# battery_regulator.net
KiCad netlist of a schematic drawn in Altium Designer
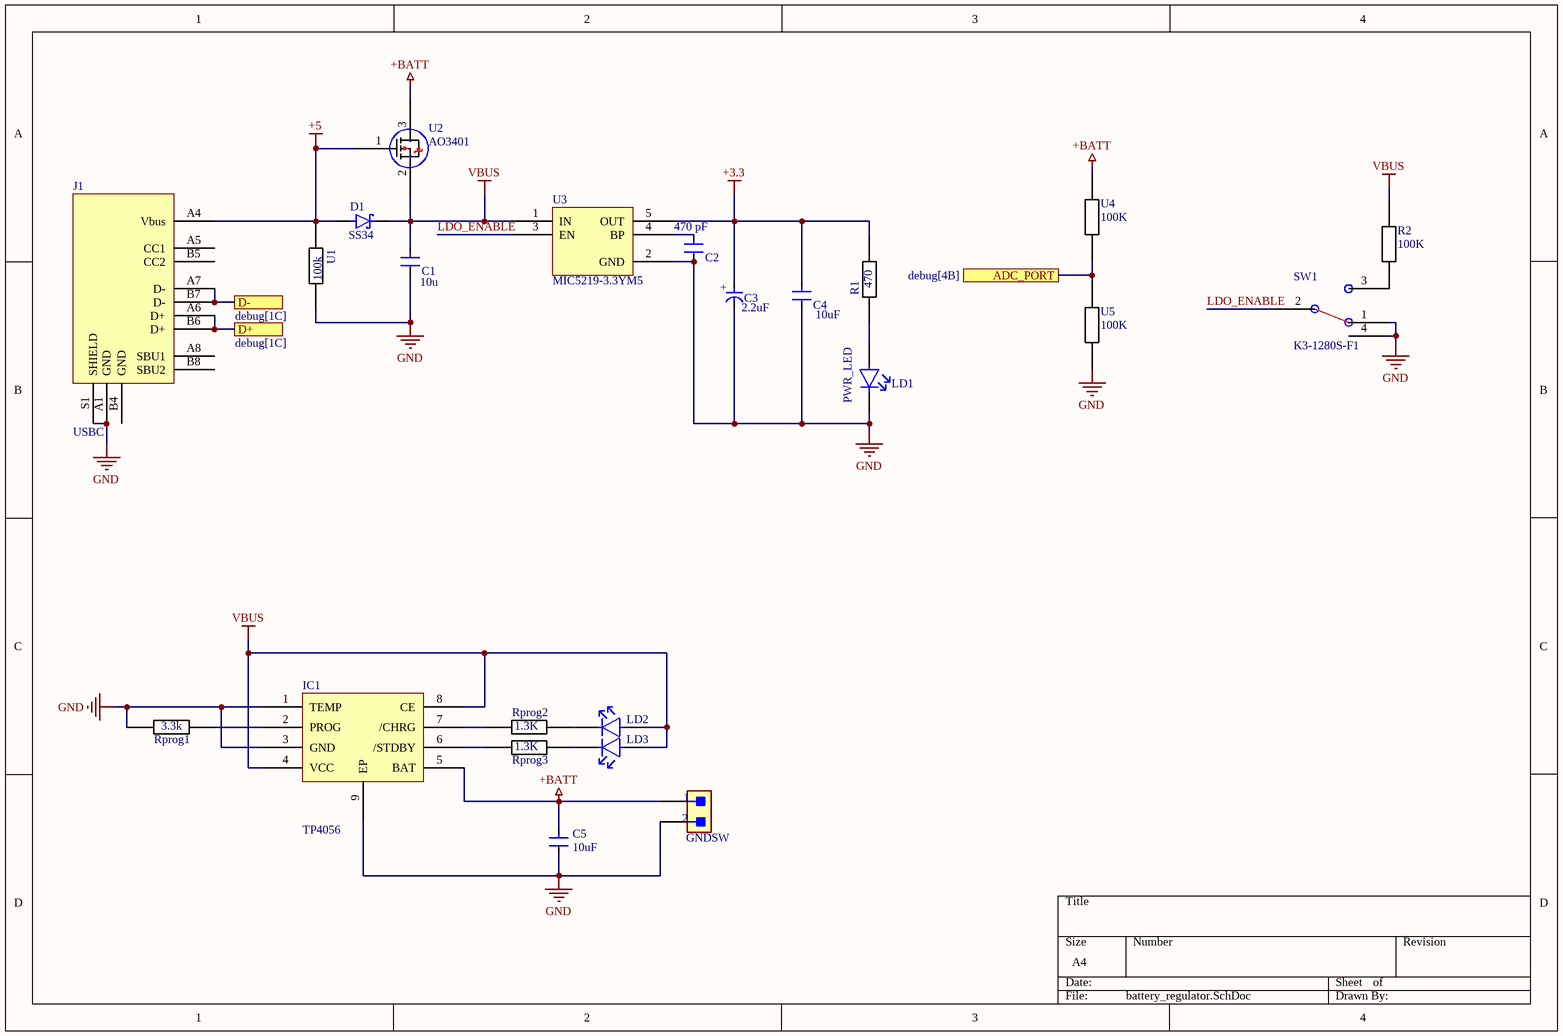
[diagram p0: battery_regulator.SchDoc]

(export (version "E")
  (design (tool "Eeschema 10.0.6"))
  (components
    (comp (ref "C1")
      (value "10u")
      (footprint "res0805ph")
      (fields (field (name "TOLERANCE") "20%"))
      (libsource (lib "LibraryTechnologie (1)") (part "CER Capacitor_1"))
    )
    (comp (ref "C2")
      (value "470 pF")
      (footprint "res0805ph")
      (fields (field (name "TOLERANCE") "20%"))
      (libsource (lib "LibraryTechnologie (1)") (part "CER Capacitor_1"))
    )
    (comp (ref "C3")
      (value "2.2uF")
      (footprint "res0805ph")
      (description "47uF 6.3V  ±20% 1.1Ω 2917  SMD Tantalum Capacitor")
      (fields (field (name "TOLERANCE") "20%"))
      (libsource (lib "LibraryTechnologie (1)") (part "Elco+tantaal_1"))
    )
    (comp (ref "C4")
      (value "10uF")
      (footprint "res0805ph")
      (fields (field (name "TOLERANCE") "20%"))
      (libsource (lib "LibraryTechnologie (1)") (part "CER Capacitor_1"))
    )
    (comp (ref "C5")
      (value "10uF")
      (footprint "res0805ph")
      (fields (field (name "TOLERANCE") "20%"))
      (libsource (lib "LibraryTechnologie (1)") (part "CER Capacitor_1"))
    )
    (comp (ref "D1") (value "SS34") (footprint "DIOM7959X265N") (libsource (lib "Dronesch") (part "SS34")))
    (comp (ref "GNDSW")
      (value "TMM-102-02-L-S")
      (footprint "JST_B2B-XH-A_(LF)(SN)")
      (description "CONN HEADER VERT 2POS 2MM")
      (libsource (lib "LibraryTechnologie (1)") (part "Connector 1x2_1"))
    )
    (comp (ref "IC1")
      (value "TP4056")
      (footprint "SOP127P600X175-9N")
      (libsource (lib "LibraryTechnologie (1)") (part "TP4056"))
    )
    (comp (ref "J1")
      (value "USBC")
      (footprint "SHENZHEN-CHUANGQIN-TECHNOLOGY_CQ-USB-C16PSMT01")
      (libsource (lib "Dronesch") (part "USBC"))
    )
    (comp (ref "LD1")
      (value "PWR_LED")
      (footprint "res0805ph")
      (description "LED GREEN CLEAR CHIP SMD")
      (libsource (lib "LibraryTechnologie (1)") (part "LED_1"))
    )
    (comp (ref "LD2")
      (value "APT1608ZGCK")
      (footprint "res0805ph")
      (description "LED GREEN CLEAR CHIP SMD")
      (libsource (lib "LibraryTechnologie (1)") (part "LED_1"))
    )
    (comp (ref "LD3")
      (value "APT1608ZGCK")
      (footprint "res0805ph")
      (description "LED GREEN CLEAR CHIP SMD")
      (libsource (lib "LibraryTechnologie (1)") (part "LED_1"))
    )
    (comp (ref "R1")
      (value "470")
      (footprint "res0805ph")
      (description "RES SMD 5.9K OHM 1% 1/4W 1206")
      (fields
        (field (name "OCTOPART") "https://octopart.com/ac1206fr-075k9l-yageo-30511161")
        (field (name "MANUFACTURER") "Yageo")
      )
      (libsource (lib "LibraryTechnologie (1)") (part "Weerstand_1"))
    )
    (comp (ref "R2")
      (value "100K")
      (footprint "res0805ph")
      (description "RES SMD 5.9K OHM 1% 1/4W 1206")
      (fields
        (field (name "OCTOPART") "https://octopart.com/ac1206fr-075k9l-yageo-30511161")
        (field (name "MANUFACTURER") "Yageo")
      )
      (libsource (lib "LibraryTechnologie (1)") (part "Weerstand_1"))
    )
    (comp (ref "Rprog1")
      (value "3.3k")
      (footprint "res0805ph")
      (description "RES SMD 5.9K OHM 1% 1/4W 1206")
      (fields
        (field (name "OCTOPART") "https://octopart.com/ac1206fr-075k9l-yageo-30511161")
        (field (name "MANUFACTURER") "Yageo")
      )
      (libsource (lib "LibraryTechnologie (1)") (part "Weerstand_1"))
    )
    (comp (ref "Rprog2")
      (value "1.3K")
      (footprint "res0805ph")
      (description "RES SMD 5.9K OHM 1% 1/4W 1206")
      (fields
        (field (name "OCTOPART") "https://octopart.com/ac1206fr-075k9l-yageo-30511161")
        (field (name "MANUFACTURER") "Yageo")
      )
      (libsource (lib "LibraryTechnologie (1)") (part "Weerstand_1"))
    )
    (comp (ref "Rprog3")
      (value "1.3K")
      (footprint "res0805ph")
      (description "RES SMD 5.9K OHM 1% 1/4W 1206")
      (fields
        (field (name "OCTOPART") "https://octopart.com/ac1206fr-075k9l-yageo-30511161")
        (field (name "MANUFACTURER") "Yageo")
      )
      (libsource (lib "LibraryTechnologie (1)") (part "Weerstand_1"))
    )
    (comp (ref "SW1")
      (value "K3-1280S-F1")
      (footprint "SW-SMD_K3-1280S-K1")
      (libsource (lib "Dronesch") (part "Switch"))
    )
    (comp (ref "U1")
      (value "100k")
      (footprint "res0805ph")
      (description "RES SMD 5.9K OHM 1% 1/4W 1206")
      (fields
        (field (name "OCTOPART") "https://octopart.com/ac1206fr-075k9l-yageo-30511161")
        (field (name "MANUFACTURER") "Yageo")
      )
      (libsource (lib "LibraryTechnologie (1)") (part "Weerstand_1"))
    )
    (comp (ref "U2") (value "AO3401") (footprint "SOT23-3") (libsource (lib "Dronesch") (part "Transistor")))
    (comp (ref "U3")
      (value "MIC5219-3.3YM5")
      (footprint "FP-SOT23-5LD-PL-1-IPC_C")
      (libsource (lib "Dronesch") (part "MIC5219-3.3YM5"))
    )
    (comp (ref "U4")
      (value "100K")
      (footprint "res0805ph")
      (description "RES SMD 5.9K OHM 1% 1/4W 1206")
      (fields
        (field (name "OCTOPART") "https://octopart.com/ac1206fr-075k9l-yageo-30511161")
        (field (name "MANUFACTURER") "Yageo")
      )
      (libsource (lib "LibraryTechnologie (1)") (part "Weerstand_1"))
    )
    (comp (ref "U5")
      (value "100K")
      (footprint "res0805ph")
      (description "RES SMD 5.9K OHM 1% 1/4W 1206")
      (fields
        (field (name "OCTOPART") "https://octopart.com/ac1206fr-075k9l-yageo-30511161")
        (field (name "MANUFACTURER") "Yageo")
      )
      (libsource (lib "LibraryTechnologie (1)") (part "Weerstand_1"))
    )
  )
  (nets
    (net (code "1") (name "+3.3") (class "Default")
      (node (ref "C3") (pin "2") (pinfunction "A_2") (pintype "passive"))
      (node (ref "C4") (pin "1") (pinfunction "1_1") (pintype "passive"))
      (node (ref "R1") (pin "2") (pinfunction "2_2") (pintype "passive"))
      (node (ref "U3") (pin "5") (pinfunction "OUT_5") (pintype "passive"))
    )
    (net (code "2") (name "+5") (class "Default")
      (node (ref "D1") (pin "A") (pinfunction "A_A") (pintype "passive"))
      (node (ref "J1") (pin "A4") (pinfunction "Vbus_A4") (pintype "passive"))
      (node (ref "U1") (pin "2") (pinfunction "2_2") (pintype "passive"))
      (node (ref "U2") (pin "1") (pinfunction "1_1") (pintype "passive"))
    )
    (net (code "3") (name "+BATT") (class "Default")
      (node (ref "C5") (pin "1") (pinfunction "1_1") (pintype "passive"))
      (node (ref "GNDSW") (pin "1") (pinfunction "1_1") (pintype "passive"))
      (node (ref "IC1") (pin "5") (pinfunction "BAT_5") (pintype "passive"))
      (node (ref "U2") (pin "3") (pinfunction "3_3") (pintype "passive"))
      (node (ref "U4") (pin "1") (pinfunction "1_1") (pintype "passive"))
    )
    (net (code "4") (name "/ADC_PORT") (class "Default")
      (node (ref "U4") (pin "2") (pinfunction "2_2") (pintype "passive"))
      (node (ref "U5") (pin "1") (pinfunction "1_1") (pintype "passive"))
    )
    (net (code "5") (name "/D+") (class "Default")
      (node (ref "J1") (pin "A6") (pinfunction "D+_A6") (pintype "passive"))
      (node (ref "J1") (pin "B6") (pinfunction "D+_B6") (pintype "passive"))
    )
    (net (code "6") (name "/D-") (class "Default")
      (node (ref "J1") (pin "A7") (pinfunction "D-_A7") (pintype "passive"))
      (node (ref "J1") (pin "B7") (pinfunction "D-_B7") (pintype "passive"))
    )
    (net (code "7") (name "/LDO_ENABLE") (class "Default")
      (node (ref "SW1") (pin "2") (pinfunction "21_2") (pintype "passive"))
      (node (ref "U3") (pin "3") (pinfunction "EN_3") (pintype "passive"))
    )
    (net (code "8") (name "GND") (class "Default")
      (node (ref "C1") (pin "2") (pinfunction "2_2") (pintype "passive"))
      (node (ref "C2") (pin "2") (pinfunction "2_2") (pintype "passive"))
      (node (ref "C3") (pin "1") (pinfunction "C_1") (pintype "passive"))
      (node (ref "C4") (pin "2") (pinfunction "2_2") (pintype "passive"))
      (node (ref "C5") (pin "2") (pinfunction "2_2") (pintype "passive"))
      (node (ref "GNDSW") (pin "2") (pinfunction "2_2") (pintype "passive"))
      (node (ref "IC1") (pin "1") (pinfunction "TEMP_1") (pintype "passive"))
      (node (ref "IC1") (pin "3") (pinfunction "GND_3") (pintype "passive"))
      (node (ref "IC1") (pin "9") (pinfunction "EP_9") (pintype "passive"))
      (node (ref "J1") (pin "A1") (pinfunction "GND_A1") (pintype "passive"))
      (node (ref "J1") (pin "S1") (pinfunction "SHIELD_S1") (pintype "passive"))
      (node (ref "LD1") (pin "1") (pinfunction "C_1") (pintype "passive"))
      (node (ref "Rprog1") (pin "2") (pinfunction "2_2") (pintype "passive"))
      (node (ref "SW1") (pin "1") (pinfunction "23_1") (pintype "passive"))
      (node (ref "SW1") (pin "4") (pinfunction "24_4") (pintype "passive"))
      (node (ref "U1") (pin "1") (pinfunction "1_1") (pintype "passive"))
      (node (ref "U3") (pin "2") (pinfunction "GND_2") (pintype "passive"))
      (node (ref "U5") (pin "2") (pinfunction "2_2") (pintype "passive"))
    )
    (net (code "9") (name "Net-(IC1-PROG)") (class "Default")
      (node (ref "IC1") (pin "2") (pinfunction "PROG_2") (pintype "passive"))
      (node (ref "Rprog1") (pin "1") (pinfunction "1_1") (pintype "passive"))
    )
    (net (code "10") (name "Net-(IC1-{slash}CHRG)") (class "Default")
      (node (ref "IC1") (pin "7") (pinfunction "/CHRG_7") (pintype "passive"))
      (node (ref "Rprog2") (pin "2") (pinfunction "2_2") (pintype "passive"))
    )
    (net (code "11") (name "Net-(IC1-{slash}STDBY)") (class "Default")
      (node (ref "IC1") (pin "6") (pinfunction "/STDBY_6") (pintype "passive"))
      (node (ref "Rprog3") (pin "2") (pinfunction "2_2") (pintype "passive"))
    )
    (net (code "12") (name "Net-(LD1-A)") (class "Default")
      (node (ref "LD1") (pin "2") (pinfunction "A_2") (pintype "passive"))
      (node (ref "R1") (pin "1") (pinfunction "1_1") (pintype "passive"))
    )
    (net (code "13") (name "Net-(LD2-C)") (class "Default")
      (node (ref "LD2") (pin "1") (pinfunction "C_1") (pintype "passive"))
      (node (ref "Rprog2") (pin "1") (pinfunction "1_1") (pintype "passive"))
    )
    (net (code "14") (name "Net-(LD3-C)") (class "Default")
      (node (ref "LD3") (pin "1") (pinfunction "C_1") (pintype "passive"))
      (node (ref "Rprog3") (pin "1") (pinfunction "1_1") (pintype "passive"))
    )
    (net (code "15") (name "Net-(SW1-22)") (class "Default")
      (node (ref "R2") (pin "2") (pinfunction "2_2") (pintype "passive"))
      (node (ref "SW1") (pin "3") (pinfunction "22_3") (pintype "passive"))
    )
    (net (code "16") (name "Net-(U3-BP)") (class "Default")
      (node (ref "C2") (pin "1") (pinfunction "1_1") (pintype "passive"))
      (node (ref "U3") (pin "4") (pinfunction "BP_4") (pintype "passive"))
    )
    (net (code "17") (name "VBUS") (class "Default")
      (node (ref "C1") (pin "1") (pinfunction "1_1") (pintype "passive"))
      (node (ref "D1") (pin "C") (pinfunction "K_C") (pintype "passive"))
      (node (ref "IC1") (pin "4") (pinfunction "VCC_4") (pintype "passive"))
      (node (ref "IC1") (pin "8") (pinfunction "CE_8") (pintype "passive"))
      (node (ref "LD2") (pin "2") (pinfunction "A_2") (pintype "passive"))
      (node (ref "LD3") (pin "2") (pinfunction "A_2") (pintype "passive"))
      (node (ref "R2") (pin "1") (pinfunction "1_1") (pintype "passive"))
      (node (ref "U2") (pin "2") (pinfunction "2_2") (pintype "passive"))
      (node (ref "U3") (pin "1") (pinfunction "IN_1") (pintype "passive"))
    )
    (net (code "18") (name "unconnected-(J1-CC1-PadA5)") (class "Default")
      (node (ref "J1") (pin "A5") (pinfunction "CC1_A5") (pintype "passive"))
    )
    (net (code "19") (name "unconnected-(J1-CC2-PadB5)") (class "Default")
      (node (ref "J1") (pin "B5") (pinfunction "CC2_B5") (pintype "passive"))
    )
    (net (code "20") (name "unconnected-(J1-GND-PadB4)") (class "Default")
      (node (ref "J1") (pin "B4") (pinfunction "GND_B4") (pintype "passive"))
    )
    (net (code "21") (name "unconnected-(J1-SBU1-PadA8)") (class "Default")
      (node (ref "J1") (pin "A8") (pinfunction "SBU1_A8") (pintype "passive"))
    )
    (net (code "22") (name "unconnected-(J1-SBU2-PadB8)") (class "Default")
      (node (ref "J1") (pin "B8") (pinfunction "SBU2_B8") (pintype "passive"))
    )
  )
)
